# regulators.net
KiCad netlist of a schematic drawn in Altium Designer
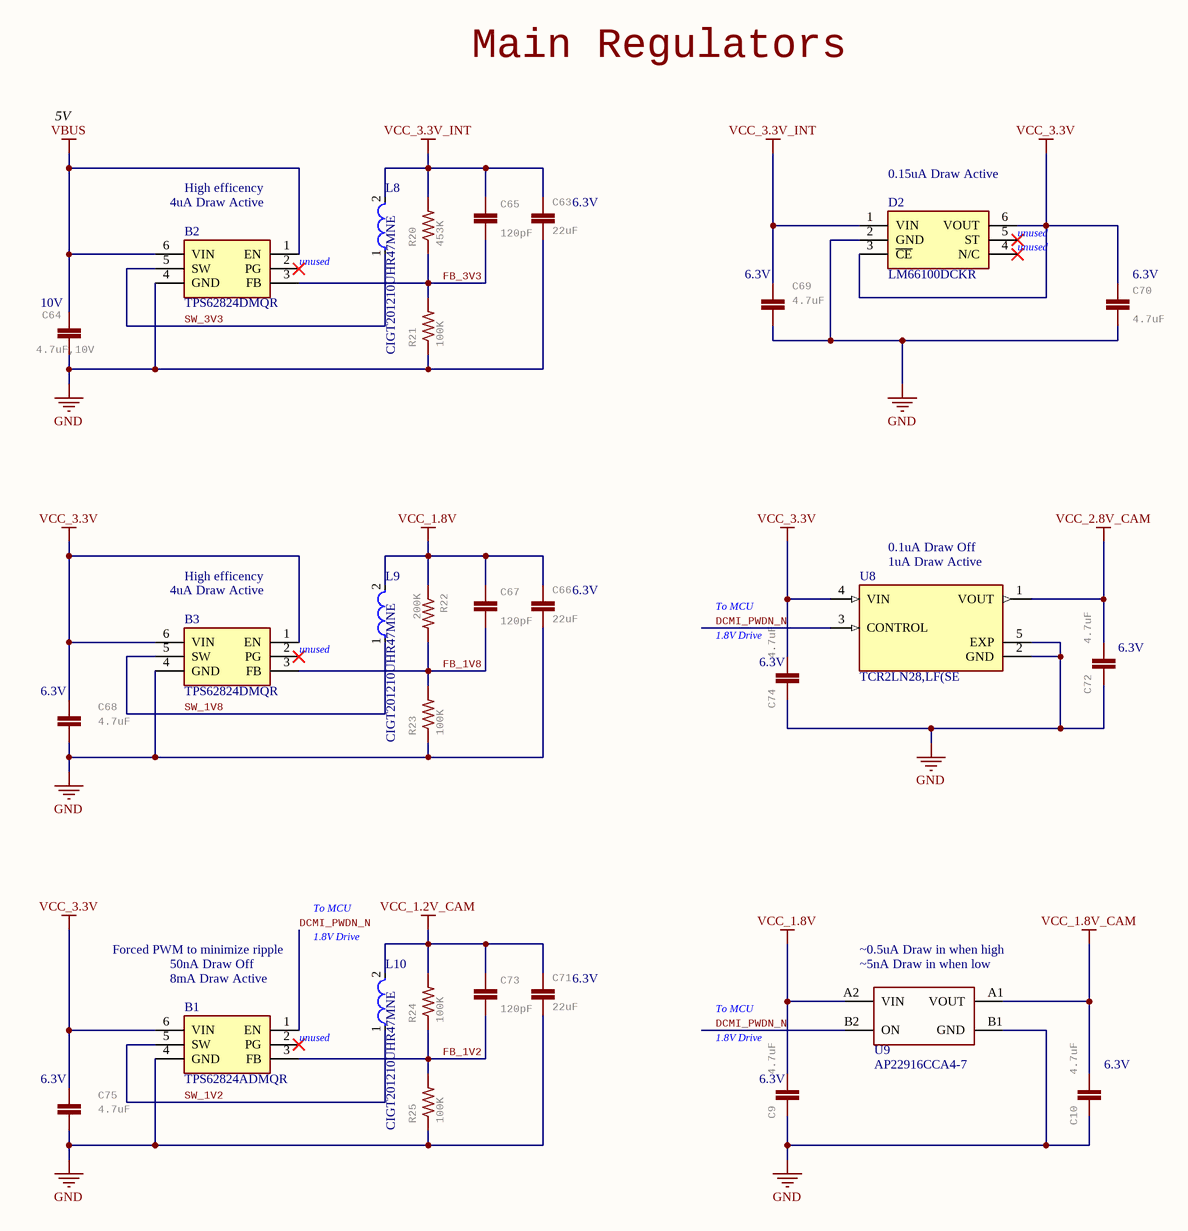
[diagram p0: regulators.SchDoc]

(export (version "E")
  (design (tool "Eeschema 10.0.6"))
  (components
    (comp (ref "B1")
      (value "TPS62824ADMQR")
      (footprint "TPS62826ADMQR")
      (fields
        (field (name "MOUSER PART NUMBER") "595-TPS62824DMQR")
        (field (name "MANUFACTURER_PART_NUMBER") "TPS62824DMQR")
      )
      (libsource (lib "openmv-ae3") (part "TPS62826ADMQR"))
    )
    (comp (ref "B2")
      (value "TPS62824DMQR")
      (footprint "TPS62826ADMQR")
      (fields
        (field (name "MOUSER PART NUMBER") "595-TPS62826DMQR")
        (field (name "MANUFACTURER_PART_NUMBER") "TPS62826DMQR")
      )
      (libsource (lib "openmv-ae3") (part "TPS62826ADMQR"))
    )
    (comp (ref "B3")
      (value "TPS62824DMQR")
      (footprint "TPS62826ADMQR")
      (fields (field (name "MOUSER PART NUMBER") "595-TPS62824DMQR"))
      (libsource (lib "openmv-ae3") (part "TPS62826ADMQR"))
    )
    (comp (ref "C9")
      (value "4.7uF")
      (footprint "0402-CAP")
      (description "0402 (1005 Metric) Nick Garner - TeleSense")
      (fields (field (name "MPN") "JMK105BBJ475MV-F"))
      (libsource (lib "openmv-ae3") (part "CAP_0402"))
    )
    (comp (ref "C10")
      (value "4.7uF")
      (footprint "0402-CAP")
      (description "0402 (1005 Metric) Nick Garner - TeleSense")
      (fields (field (name "MPN") "JMK105BBJ475MV-F"))
      (libsource (lib "openmv-ae3") (part "CAP_0402"))
    )
    (comp (ref "C63")
      (value "22uF")
      (footprint "0805")
      (fields (field (name "MPN") "CL21A226MQQNNNE"))
      (libsource (lib "openmv-ae3") (part "22UF-0805-6.3V-20%"))
    )
    (comp (ref "C64")
      (value "4.7uF,10V")
      (footprint "0402-CAP")
      (description "CapacitorStandard 0603 ceramic capacitor, and 0.1\" leaded capacitor.")
      (fields (field (name "MPN") "CL05A475MP5NRNC") (field (name "LIBRARYNAME") "sfe"))
      (libsource (lib "") (part "CAP0402-CAP_1"))
    )
    (comp (ref "C65")
      (value "120pF")
      (footprint "C0201")
      (fields (field (name "MPN") "GRM033R71H121KA12D") (field (name "LIBRARYNAME") "sfe"))
      (libsource (lib "openmv-ae3") (part "CAP0402-CAP"))
    )
    (comp (ref "C66")
      (value "22uF")
      (footprint "0805")
      (fields (field (name "MPN") "CL21A226MQQNNNE"))
      (libsource (lib "openmv-ae3") (part "22UF-0805-6.3V-20%"))
    )
    (comp (ref "C67")
      (value "120pF")
      (footprint "C0201")
      (fields (field (name "MPN") "GRM033R71H121KA12D") (field (name "LIBRARYNAME") "sfe"))
      (libsource (lib "openmv-ae3") (part "CAP0402-CAP"))
    )
    (comp (ref "C68")
      (value "4.7uF")
      (footprint "0402-CAP")
      (description "CapacitorStandard 0603 ceramic capacitor, and 0.1\" leaded capacitor.")
      (fields (field (name "MPN") "JMK105BBJ475MV-F") (field (name "LIBRARYNAME") "sfe"))
      (libsource (lib "openmv-ae3") (part "CAP0402-CAP"))
    )
    (comp (ref "C69")
      (value "4.7uF")
      (footprint "0402-CAP")
      (description "CapacitorStandard 0603 ceramic capacitor, and 0.1\" leaded capacitor.")
      (fields (field (name "MPN") "JMK105BBJ475MV-F") (field (name "LIBRARYNAME") "sfe"))
      (libsource (lib "openmv-ae3") (part "CAP0402-CAP"))
    )
    (comp (ref "C70")
      (value "4.7uF")
      (footprint "0402-CAP")
      (description "CapacitorStandard 0603 ceramic capacitor, and 0.1\" leaded capacitor.")
      (fields (field (name "MPN") "JMK105BBJ475MV-F") (field (name "LIBRARYNAME") "sfe"))
      (libsource (lib "openmv-ae3") (part "CAP0402-CAP"))
    )
    (comp (ref "C71")
      (value "22uF")
      (footprint "0805")
      (fields (field (name "MPN") "CL21A226MQQNNNE"))
      (libsource (lib "openmv-ae3") (part "22UF-0805-6.3V-20%"))
    )
    (comp (ref "C72")
      (value "4.7uF")
      (footprint "0402-CAP")
      (description "0402 (1005 Metric) Nick Garner - TeleSense")
      (fields (field (name "MPN") "JMK105BBJ475MV-F"))
      (libsource (lib "openmv-ae3") (part "CAP_0402"))
    )
    (comp (ref "C73")
      (value "120pF")
      (footprint "C0201")
      (fields (field (name "MPN") "GRM033R71H121KA12D") (field (name "LIBRARYNAME") "sfe"))
      (libsource (lib "openmv-ae3") (part "CAP0402-CAP"))
    )
    (comp (ref "C74")
      (value "4.7uF")
      (footprint "0402-CAP")
      (description "0402 (1005 Metric) Nick Garner - TeleSense")
      (fields (field (name "MPN") "JMK105BBJ475MV-F"))
      (libsource (lib "openmv-ae3") (part "CAP_0402"))
    )
    (comp (ref "C75")
      (value "4.7uF")
      (footprint "0402-CAP")
      (description "CapacitorStandard 0603 ceramic capacitor, and 0.1\" leaded capacitor.")
      (fields (field (name "MPN") "JMK105BBJ475MV-F") (field (name "LIBRARYNAME") "sfe"))
      (libsource (lib "openmv-ae3") (part "CAP0402-CAP"))
    )
    (comp (ref "D2")
      (value "LM66100DCKR")
      (footprint "SamacSys:SOP65P210X110-6N")
      (description "Diode")
      (fields
        (field (name "MANUFACTURER_PART_NUMBER") "c")
        (field (name "MOUSER PART NUMBER") "595-LM66100DCKR")
      )
      (libsource (lib "openmv-ae3") (part "LM66100DCKR"))
    )
    (comp (ref "L8")
      (value "CIGT201210UHR47MNE")
      (footprint "0805")
      (description "Power Inductor : LxW size(mm) 2012 Thickness1 Inductance (uH) 20%: 0.47")
      (fields (field (name "TOLERANCE") "20%"))
      (libsource (lib "openmv-ae3") (part "CMP-00002-1"))
    )
    (comp (ref "L9")
      (value "CIGT201210UHR47MNE")
      (footprint "0805")
      (description "Power Inductor : LxW size(mm) 2012 Thickness1 Inductance (uH) 20%: 0.47")
      (fields (field (name "TOLERANCE") "20%"))
      (libsource (lib "openmv-ae3") (part "CMP-00002-1"))
    )
    (comp (ref "L10")
      (value "CIGT201210UHR47MNE")
      (footprint "0805")
      (description "Power Inductor : LxW size(mm) 2012 Thickness1 Inductance (uH) 20%: 0.47")
      (fields (field (name "TOLERANCE") "20%"))
      (libsource (lib "openmv-ae3") (part "CMP-00002-1"))
    )
    (comp (ref "R20")
      (value "453K")
      (footprint "R0201")
      (fields (field (name "MPN") "ERJ-1GNF4533C") (field (name "LIBRARYNAME") "sfe"))
      (libsource (lib "openmv-ae3") (part "RESISTOR0402-RES"))
    )
    (comp (ref "R21")
      (value "100K")
      (footprint "R0201")
      (fields (field (name "MPN") "RMCF0201FT100K") (field (name "LIBRARYNAME") "sfe"))
      (libsource (lib "openmv-ae3") (part "RESISTOR0402-RES"))
    )
    (comp (ref "R22")
      (value "200K")
      (footprint "R0201")
      (fields (field (name "MPN") "RC0201JR-07200KL") (field (name "LIBRARYNAME") "sfe"))
      (libsource (lib "openmv-ae3") (part "RESISTOR0402-RES"))
    )
    (comp (ref "R23")
      (value "100K")
      (footprint "R0201")
      (fields (field (name "MPN") "RMCF0201FT100K") (field (name "LIBRARYNAME") "sfe"))
      (libsource (lib "openmv-ae3") (part "RESISTOR0402-RES"))
    )
    (comp (ref "R24")
      (value "100K")
      (footprint "R0201")
      (fields (field (name "MPN") "RMCF0201FT100K") (field (name "LIBRARYNAME") "sfe"))
      (libsource (lib "openmv-ae3") (part "RESISTOR0402-RES"))
    )
    (comp (ref "R25")
      (value "100K")
      (footprint "R0201")
      (fields (field (name "MPN") "RMCF0201FT100K") (field (name "LIBRARYNAME") "sfe"))
      (libsource (lib "openmv-ae3") (part "RESISTOR0402-RES"))
    )
    (comp (ref "U8")
      (value "TCR2LN28,LF(SE")
      (footprint "VREG_TCR2LN30_LF")
      (description "Linear Voltage Regulator IC Positive Fixed 1 Output 200mA 4-SDFN (0.8x0.8)")
      (fields (field (name "MF") "Toshiba Semiconductor"))
      (libsource (lib "openmv-ae3") (part "TCR2LN30_LF"))
    )
    (comp (ref "U9")
      (value "PMOS Load Switch")
      (footprint "AP22916CCA4-7")
      (fields
        (field (name "MPN") "AP22916CCA4-7")
        (field (name "MF") "Diodes Inc")
        (field (name "PART NUMBER") "AP22916CCA4-7")
      )
      (libsource (lib "openmv-ae3") (part "AP22916CCA4-7"))
    )
  )
  (nets
    (net (code "1") (name "/DCMI_PWDN_N") (class "Default")
      (node (ref "B1") (pin "1") (pinfunction "EN_1") (pintype "passive"))
      (node (ref "U8") (pin "3") (pinfunction "CONTROL_3") (pintype "input"))
      (node (ref "U9") (pin "B2") (pinfunction "ON_B2") (pintype "passive"))
    )
    (net (code "2") (name "/FB_1V2") (class "Default")
      (node (ref "B1") (pin "3") (pinfunction "FB_3") (pintype "passive"))
      (node (ref "C73") (pin "1") (pinfunction "1_1") (pintype "passive"))
      (node (ref "R24") (pin "1") (pinfunction "1_1") (pintype "passive"))
      (node (ref "R25") (pin "2") (pinfunction "2_2") (pintype "passive"))
    )
    (net (code "3") (name "/FB_1V8") (class "Default")
      (node (ref "B3") (pin "3") (pinfunction "FB_3") (pintype "passive"))
      (node (ref "C67") (pin "1") (pinfunction "1_1") (pintype "passive"))
      (node (ref "R22") (pin "2") (pinfunction "2_2") (pintype "passive"))
      (node (ref "R23") (pin "2") (pinfunction "2_2") (pintype "passive"))
    )
    (net (code "4") (name "/FB_3V3") (class "Default")
      (node (ref "B2") (pin "3") (pinfunction "FB_3") (pintype "passive"))
      (node (ref "C65") (pin "1") (pinfunction "1_1") (pintype "passive"))
      (node (ref "R20") (pin "1") (pinfunction "1_1") (pintype "passive"))
      (node (ref "R21") (pin "2") (pinfunction "2_2") (pintype "passive"))
    )
    (net (code "5") (name "/SW_1V2") (class "Default")
      (node (ref "B1") (pin "5") (pinfunction "SW_5") (pintype "passive"))
      (node (ref "L10") (pin "1") (pinfunction "1_1") (pintype "passive"))
    )
    (net (code "6") (name "/SW_1V8") (class "Default")
      (node (ref "B3") (pin "5") (pinfunction "SW_5") (pintype "passive"))
      (node (ref "L9") (pin "1") (pinfunction "1_1") (pintype "passive"))
    )
    (net (code "7") (name "/SW_3V3") (class "Default")
      (node (ref "B2") (pin "5") (pinfunction "SW_5") (pintype "passive"))
      (node (ref "L8") (pin "1") (pinfunction "1_1") (pintype "passive"))
    )
    (net (code "8") (name "GND") (class "Default")
      (node (ref "B1") (pin "4") (pinfunction "GND_4") (pintype "passive"))
      (node (ref "B2") (pin "4") (pinfunction "GND_4") (pintype "passive"))
      (node (ref "B3") (pin "4") (pinfunction "GND_4") (pintype "passive"))
      (node (ref "C10") (pin "1") (pinfunction "1_1") (pintype "passive"))
      (node (ref "C63") (pin "2") (pinfunction "2_2") (pintype "passive"))
      (node (ref "C64") (pin "2") (pinfunction "2_2") (pintype "passive"))
      (node (ref "C66") (pin "2") (pinfunction "2_2") (pintype "passive"))
      (node (ref "C68") (pin "1") (pinfunction "1_1") (pintype "passive"))
      (node (ref "C69") (pin "1") (pinfunction "1_1") (pintype "passive"))
      (node (ref "C70") (pin "1") (pinfunction "1_1") (pintype "passive"))
      (node (ref "C71") (pin "2") (pinfunction "2_2") (pintype "passive"))
      (node (ref "C72") (pin "1") (pinfunction "1_1") (pintype "passive"))
      (node (ref "C74") (pin "1") (pinfunction "1_1") (pintype "passive"))
      (node (ref "C75") (pin "1") (pinfunction "1_1") (pintype "passive"))
      (node (ref "C9") (pin "1") (pinfunction "1_1") (pintype "passive"))
      (node (ref "D2") (pin "2") (pinfunction "GND_2") (pintype "passive"))
      (node (ref "R21") (pin "1") (pinfunction "1_1") (pintype "passive"))
      (node (ref "R23") (pin "1") (pinfunction "1_1") (pintype "passive"))
      (node (ref "R25") (pin "1") (pinfunction "1_1") (pintype "passive"))
      (node (ref "U8") (pin "2") (pinfunction "GND_2") (pintype "power_in"))
      (node (ref "U8") (pin "5") (pinfunction "EXP_5") (pintype "power_in"))
      (node (ref "U9") (pin "B1") (pinfunction "GND_B1") (pintype "passive"))
    )
    (net (code "9") (name "VBUS") (class "Default")
      (node (ref "B2") (pin "1") (pinfunction "EN_1") (pintype "passive"))
      (node (ref "B2") (pin "6") (pinfunction "VIN_6") (pintype "passive"))
      (node (ref "C64") (pin "1") (pinfunction "1_1") (pintype "passive"))
    )
    (net (code "10") (name "VCC_1.2V_CAM") (class "Default")
      (node (ref "C71") (pin "1") (pinfunction "1_1") (pintype "passive"))
      (node (ref "C73") (pin "2") (pinfunction "2_2") (pintype "passive"))
      (node (ref "L10") (pin "2") (pinfunction "2_2") (pintype "passive"))
      (node (ref "R24") (pin "2") (pinfunction "2_2") (pintype "passive"))
    )
    (net (code "11") (name "VCC_1.8V") (class "Default")
      (node (ref "C66") (pin "1") (pinfunction "1_1") (pintype "passive"))
      (node (ref "C67") (pin "2") (pinfunction "2_2") (pintype "passive"))
      (node (ref "C9") (pin "2") (pinfunction "2_2") (pintype "passive"))
      (node (ref "L9") (pin "2") (pinfunction "2_2") (pintype "passive"))
      (node (ref "R22") (pin "1") (pinfunction "1_1") (pintype "passive"))
      (node (ref "U9") (pin "A2") (pinfunction "VIN_A2") (pintype "passive"))
    )
    (net (code "12") (name "VCC_1.8V_CAM") (class "Default")
      (node (ref "C10") (pin "2") (pinfunction "2_2") (pintype "passive"))
      (node (ref "U9") (pin "A1") (pinfunction "VOUT_A1") (pintype "passive"))
    )
    (net (code "13") (name "VCC_2.8V_CAM") (class "Default")
      (node (ref "C72") (pin "2") (pinfunction "2_2") (pintype "passive"))
      (node (ref "U8") (pin "1") (pinfunction "VOUT_1") (pintype "output"))
    )
    (net (code "14") (name "VCC_3.3V") (class "Default")
      (node (ref "B1") (pin "6") (pinfunction "VIN_6") (pintype "passive"))
      (node (ref "B3") (pin "1") (pinfunction "EN_1") (pintype "passive"))
      (node (ref "B3") (pin "6") (pinfunction "VIN_6") (pintype "passive"))
      (node (ref "C68") (pin "2") (pinfunction "2_2") (pintype "passive"))
      (node (ref "C70") (pin "2") (pinfunction "2_2") (pintype "passive"))
      (node (ref "C74") (pin "2") (pinfunction "2_2") (pintype "passive"))
      (node (ref "C75") (pin "2") (pinfunction "2_2") (pintype "passive"))
      (node (ref "D2") (pin "3") (pinfunction "~{CE}_3") (pintype "passive"))
      (node (ref "D2") (pin "6") (pinfunction "VOUT_6") (pintype "passive"))
      (node (ref "U8") (pin "4") (pinfunction "VIN_4") (pintype "input"))
    )
    (net (code "15") (name "VCC_3.3V_INT") (class "Default")
      (node (ref "C63") (pin "1") (pinfunction "1_1") (pintype "passive"))
      (node (ref "C65") (pin "2") (pinfunction "2_2") (pintype "passive"))
      (node (ref "C69") (pin "2") (pinfunction "2_2") (pintype "passive"))
      (node (ref "D2") (pin "1") (pinfunction "VIN_1") (pintype "passive"))
      (node (ref "L8") (pin "2") (pinfunction "2_2") (pintype "passive"))
      (node (ref "R20") (pin "2") (pinfunction "2_2") (pintype "passive"))
    )
    (net (code "16") (name "unconnected-(B1-PG-Pad2)") (class "Default")
      (node (ref "B1") (pin "2") (pinfunction "PG_2") (pintype "passive+no_connect"))
    )
    (net (code "17") (name "unconnected-(B2-PG-Pad2)") (class "Default")
      (node (ref "B2") (pin "2") (pinfunction "PG_2") (pintype "passive+no_connect"))
    )
    (net (code "18") (name "unconnected-(B3-PG-Pad2)") (class "Default")
      (node (ref "B3") (pin "2") (pinfunction "PG_2") (pintype "passive+no_connect"))
    )
    (net (code "19") (name "unconnected-(D2-N{slash}C-Pad4)") (class "Default")
      (node (ref "D2") (pin "4") (pinfunction "N/C_4") (pintype "passive+no_connect"))
    )
    (net (code "20") (name "unconnected-(D2-ST-Pad5)") (class "Default")
      (node (ref "D2") (pin "5") (pinfunction "ST_5") (pintype "passive+no_connect"))
    )
  )
)
